# chonkeegamp.net
KiCad netlist of a schematic drawn in EAGLE
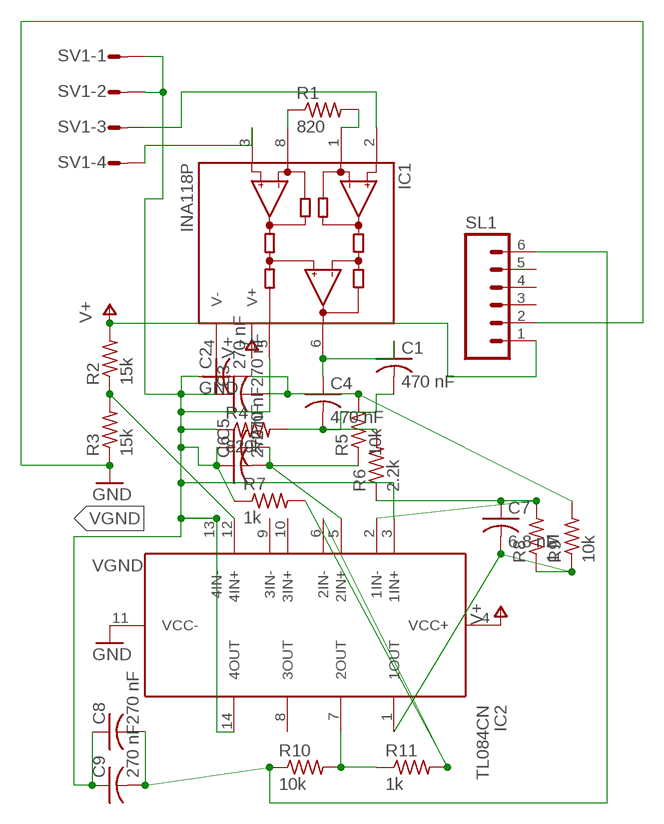
[diagram p0: schematic, sheet 1]

(export (version "E")
  (design (tool "Eeschema 10.0.6"))
  (components
    (comp (ref "C1")
      (value "470 nF")
      (footprint "eagle-import:C050-024X044")
      (fields (field (name "MF") "VISHAY") (field (name "MPN") "BFC237390043"))
      (libsource (lib "eagle-import") (part "C-US050-024X044"))
    )
    (comp (ref "C2")
      (value "270 nF")
      (footprint "eagle-import:C050-024X044")
      (fields (field (name "MF") "VISHAY") (field (name "MPN") "BFC237390132"))
      (libsource (lib "eagle-import") (part "C-US050-024X044"))
    )
    (comp (ref "C3")
      (value "270 nF")
      (footprint "eagle-import:C050-024X044")
      (fields (field (name "MF") "VISHAY") (field (name "MPN") "BFC237390132"))
      (libsource (lib "eagle-import") (part "C-US050-024X044"))
    )
    (comp (ref "C4")
      (value "470 nF")
      (footprint "eagle-import:C050-024X044")
      (fields (field (name "MF") "VISHAY") (field (name "MPN") "BFC237390043"))
      (libsource (lib "eagle-import") (part "C-US050-024X044"))
    )
    (comp (ref "C5")
      (value "270 nF")
      (footprint "eagle-import:C050-024X044")
      (fields (field (name "MF") "VISHAY") (field (name "MPN") "BFC237390132"))
      (libsource (lib "eagle-import") (part "C-US050-024X044"))
    )
    (comp (ref "C6")
      (value "270 nF")
      (footprint "eagle-import:C050-024X044")
      (fields (field (name "MF") "VISHAY") (field (name "MPN") "BFC237390132"))
      (libsource (lib "eagle-import") (part "C-US050-024X044"))
    )
    (comp (ref "C7")
      (value "6.8 nF")
      (footprint "eagle-import:C050-024X044")
      (fields (field (name "MF") "KEMET") (field (name "MPN") "C315C682K1R5TA"))
      (libsource (lib "eagle-import") (part "C-US050-024X044"))
    )
    (comp (ref "C8")
      (value "270 nF")
      (footprint "eagle-import:C050-024X044")
      (fields (field (name "MF") "VISHAY") (field (name "MPN") "BFC237390132"))
      (libsource (lib "eagle-import") (part "C-US050-024X044"))
    )
    (comp (ref "C9")
      (value "270 nF")
      (footprint "eagle-import:C050-024X044")
      (fields (field (name "MF") "VISHAY") (field (name "MPN") "BFC237390132"))
      (libsource (lib "eagle-import") (part "C-US050-024X044"))
    )
    (comp (ref "IC1")
      (value "INA118P")
      (footprint "eagle-import:DIL08")
      (fields (field (name "MF") "TEXAS INSTRUMENTS") (field (name "OC_NEWARK") "34AH0811"))
      (libsource (lib "eagle-import") (part "INA118P"))
    )
    (comp (ref "IC2")
      (value "TL084CN")
      (footprint "eagle-import:DIP794W53P254L1930H508Q14N")
      (fields (field (name "MOUSER_PART_NUMBER") "595-TL084CN") (field (name "MF") "TEXAS INSTRUMENTS"))
      (libsource (lib "eagle-import") (part "TL084CN"))
    )
    (comp (ref "R1")
      (value "820")
      (footprint "eagle-import:0207_7")
      (fields (field (name "MF") "MULTICOMP PRO") (field (name "MPN") "MCF 0.5W 820R"))
      (libsource (lib "eagle-import") (part "R-US_0207/7"))
    )
    (comp (ref "R2")
      (value "15k")
      (footprint "eagle-import:0207_7")
      (fields (field (name "MF") "MULTICOMP PRO") (field (name "MPN") "MCF 1W 15K"))
      (libsource (lib "eagle-import") (part "R-US_0207/7"))
    )
    (comp (ref "R3")
      (value "15k")
      (footprint "eagle-import:0207_7")
      (fields (field (name "MF") "MULTICOMP PRO") (field (name "MPN") "MCF 1W 15K"))
      (libsource (lib "eagle-import") (part "R-US_0207/7"))
    )
    (comp (ref "R4")
      (value "820k")
      (footprint "eagle-import:0207_7")
      (fields (field (name "MF") "MULTICOMP PRO") (field (name "MPN") "MCF 0.25W 820K"))
      (libsource (lib "eagle-import") (part "R-US_0207/7"))
    )
    (comp (ref "R5")
      (value "10k")
      (footprint "eagle-import:0207_7")
      (fields (field (name "MF") "MULTICOMP PRO") (field (name "MPN") "MCCFR0W4J0103A50"))
      (libsource (lib "eagle-import") (part "R-US_0207/7"))
    )
    (comp (ref "R6")
      (value "2.2k")
      (footprint "eagle-import:0207_7")
      (fields (field (name "MF") "MULTICOMP PRO") (field (name "MPN") "MCF 0.5W 2K2"))
      (libsource (lib "eagle-import") (part "R-US_0207/7"))
    )
    (comp (ref "R7")
      (value "1k")
      (footprint "eagle-import:0207_7")
      (fields (field (name "MF") "MULTICOMP PRO") (field (name "MPN") "MCCFR0S2J0102A20"))
      (libsource (lib "eagle-import") (part "R-US_0207/7"))
    )
    (comp (ref "R8")
      (value "1 M")
      (footprint "eagle-import:0207_7")
      (fields (field (name "MF") "MULTICOMP PRO") (field (name "MPN") "MCF 0.5W 1M"))
      (libsource (lib "eagle-import") (part "R-US_0207/7"))
    )
    (comp (ref "R9")
      (value "10k")
      (footprint "eagle-import:0207_7")
      (fields (field (name "MF") "MULTICOMP PRO") (field (name "MPN") "MCCFR0W4J0103A50"))
      (libsource (lib "eagle-import") (part "R-US_0207/7"))
    )
    (comp (ref "R10")
      (value "10k")
      (footprint "eagle-import:0207_7")
      (fields (field (name "MF") "MULTICOMP PRO") (field (name "MPN") "MCCFR0W4J0103A50"))
      (libsource (lib "eagle-import") (part "R-US_0207/7"))
    )
    (comp (ref "R11")
      (value "1k")
      (footprint "eagle-import:0207_7")
      (fields (field (name "MF") "MULTICOMP PRO") (field (name "MPN") "MCCFR0S2J0102A20"))
      (libsource (lib "eagle-import") (part "R-US_0207/7"))
    )
    (comp (ref "SL1")
      (value "M06")
      (footprint "eagle-import:06P")
      (libsource (lib "eagle-import") (part "M06"))
    )
    (comp (ref "SV1")
      (value "L04P")
      (footprint "eagle-import:L04P")
      (libsource (lib "eagle-import") (part "L04P"))
    )
  )
  (nets
    (net (code "1") (name "GND") (class "Default")
      (node (ref "IC1") (pin "4") (pinfunction "V-_4") (pintype "power_in"))
      (node (ref "IC2") (pin "11") (pinfunction "VCC-_11") (pintype "power_in"))
      (node (ref "R3") (pin "1") (pinfunction "1_1") (pintype "passive"))
      (node (ref "SL1") (pin "2") (pinfunction "2_2") (pintype "passive"))
    )
    (net (code "2") (name "Net-(C1-Pad2)") (class "Default")
      (node (ref "C1") (pin "2") (pinfunction "2_2") (pintype "passive"))
      (node (ref "C4") (pin "2") (pinfunction "2_2") (pintype "passive"))
      (node (ref "R4") (pin "2") (pinfunction "2_2") (pintype "passive"))
      (node (ref "R6") (pin "2") (pinfunction "2_2") (pintype "passive"))
    )
    (net (code "3") (name "Net-(C2-Pad2)") (class "Default")
      (node (ref "C2") (pin "2") (pinfunction "2_2") (pintype "passive"))
      (node (ref "C3") (pin "2") (pinfunction "2_2") (pintype "passive"))
      (node (ref "R5") (pin "2") (pinfunction "2_2") (pintype "passive"))
      (node (ref "R9") (pin "2") (pinfunction "2_2") (pintype "passive"))
    )
    (net (code "4") (name "Net-(C8-Pad2)") (class "Default")
      (node (ref "C8") (pin "2") (pinfunction "2_2") (pintype "passive"))
      (node (ref "C9") (pin "2") (pinfunction "2_2") (pintype "passive"))
      (node (ref "R10") (pin "1") (pinfunction "1_1") (pintype "passive"))
      (node (ref "SL1") (pin "6") (pinfunction "6_6") (pintype "passive"))
    )
    (net (code "5") (name "Net-(IC1-+IN)") (class "Default")
      (node (ref "IC1") (pin "3") (pinfunction "+IN_3") (pintype "input"))
      (node (ref "SV1") (pin "4") (pinfunction "S_4") (pintype "passive"))
    )
    (net (code "6") (name "Net-(IC1--IN)") (class "Default")
      (node (ref "IC1") (pin "2") (pinfunction "-IN_2") (pintype "input"))
      (node (ref "SV1") (pin "3") (pinfunction "S_3") (pintype "passive"))
    )
    (net (code "7") (name "Net-(IC1-OUT)") (class "Default")
      (node (ref "C1") (pin "1") (pinfunction "1_1") (pintype "passive"))
      (node (ref "C4") (pin "1") (pinfunction "1_1") (pintype "passive"))
      (node (ref "IC1") (pin "6") (pinfunction "OUT_6") (pintype "output"))
    )
    (net (code "8") (name "Net-(IC1-RG-Pad1)") (class "Default")
      (node (ref "IC1") (pin "1") (pinfunction "RG_1") (pintype "passive"))
      (node (ref "R1") (pin "2") (pinfunction "2_2") (pintype "passive"))
    )
    (net (code "9") (name "Net-(IC1-RG-Pad8)") (class "Default")
      (node (ref "IC1") (pin "8") (pinfunction "RG_8") (pintype "passive"))
      (node (ref "R1") (pin "1") (pinfunction "1_1") (pintype "passive"))
    )
    (net (code "10") (name "Net-(IC2-1IN-)") (class "Default")
      (node (ref "C7") (pin "1") (pinfunction "1_1") (pintype "passive"))
      (node (ref "IC2") (pin "2") (pinfunction "1IN-_2") (pintype "input"))
      (node (ref "R6") (pin "1") (pinfunction "1_1") (pintype "passive"))
      (node (ref "R8") (pin "2") (pinfunction "2_2") (pintype "passive"))
    )
    (net (code "11") (name "Net-(IC2-1OUT)") (class "Default")
      (node (ref "C7") (pin "2") (pinfunction "2_2") (pintype "passive"))
      (node (ref "IC2") (pin "1") (pinfunction "1OUT_1") (pintype "output"))
      (node (ref "R8") (pin "1") (pinfunction "1_1") (pintype "passive"))
      (node (ref "R9") (pin "1") (pinfunction "1_1") (pintype "passive"))
    )
    (net (code "12") (name "Net-(IC2-2IN+)") (class "Default")
      (node (ref "C5") (pin "2") (pinfunction "2_2") (pintype "passive"))
      (node (ref "C6") (pin "2") (pinfunction "2_2") (pintype "passive"))
      (node (ref "IC2") (pin "5") (pinfunction "2IN+_5") (pintype "input"))
      (node (ref "R5") (pin "1") (pinfunction "1_1") (pintype "passive"))
    )
    (net (code "13") (name "Net-(IC2-2IN-)") (class "Default")
      (node (ref "IC2") (pin "6") (pinfunction "2IN-_6") (pintype "input"))
      (node (ref "R11") (pin "2") (pinfunction "2_2") (pintype "passive"))
      (node (ref "R7") (pin "2") (pinfunction "2_2") (pintype "passive"))
    )
    (net (code "14") (name "Net-(IC2-2OUT)") (class "Default")
      (node (ref "IC2") (pin "7") (pinfunction "2OUT_7") (pintype "output"))
      (node (ref "R10") (pin "2") (pinfunction "2_2") (pintype "passive"))
      (node (ref "R11") (pin "1") (pinfunction "1_1") (pintype "passive"))
    )
    (net (code "15") (name "Net-(IC2-4IN+)") (class "Default")
      (node (ref "IC2") (pin "12") (pinfunction "4IN+_12") (pintype "input"))
      (node (ref "R2") (pin "1") (pinfunction "1_1") (pintype "passive"))
      (node (ref "R3") (pin "2") (pinfunction "2_2") (pintype "passive"))
    )
    (net (code "16") (name "V+") (class "Default")
      (node (ref "IC1") (pin "7") (pinfunction "V+_7") (pintype "power_in"))
      (node (ref "IC2") (pin "4") (pinfunction "VCC+_4") (pintype "power_in"))
      (node (ref "R2") (pin "2") (pinfunction "2_2") (pintype "passive"))
      (node (ref "SL1") (pin "1") (pinfunction "1_1") (pintype "passive"))
    )
    (net (code "17") (name "VGND") (class "Default")
      (node (ref "C2") (pin "1") (pinfunction "1_1") (pintype "passive"))
      (node (ref "C3") (pin "1") (pinfunction "1_1") (pintype "passive"))
      (node (ref "C5") (pin "1") (pinfunction "1_1") (pintype "passive"))
      (node (ref "C6") (pin "1") (pinfunction "1_1") (pintype "passive"))
      (node (ref "C8") (pin "1") (pinfunction "1_1") (pintype "passive"))
      (node (ref "C9") (pin "1") (pinfunction "1_1") (pintype "passive"))
      (node (ref "IC1") (pin "5") (pinfunction "REF_5") (pintype "passive"))
      (node (ref "IC2") (pin "13") (pinfunction "4IN-_13") (pintype "input"))
      (node (ref "IC2") (pin "14") (pinfunction "4OUT_14") (pintype "output"))
      (node (ref "IC2") (pin "3") (pinfunction "1IN+_3") (pintype "input"))
      (node (ref "R4") (pin "1") (pinfunction "1_1") (pintype "passive"))
      (node (ref "R7") (pin "1") (pinfunction "1_1") (pintype "passive"))
      (node (ref "SV1") (pin "1") (pinfunction "S_1") (pintype "passive"))
      (node (ref "SV1") (pin "2") (pinfunction "S_2") (pintype "passive"))
    )
    (net (code "18") (name "unconnected-(IC2-3IN+-Pad10)") (class "Default")
      (node (ref "IC2") (pin "10") (pinfunction "3IN+_10") (pintype "input"))
    )
    (net (code "19") (name "unconnected-(IC2-3IN--Pad9)") (class "Default")
      (node (ref "IC2") (pin "9") (pinfunction "3IN-_9") (pintype "input"))
    )
    (net (code "20") (name "unconnected-(IC2-3OUT-Pad8)") (class "Default")
      (node (ref "IC2") (pin "8") (pinfunction "3OUT_8") (pintype "output"))
    )
    (net (code "21") (name "unconnected-(SL1-Pad3)") (class "Default")
      (node (ref "SL1") (pin "3") (pinfunction "3_3") (pintype "passive"))
    )
    (net (code "22") (name "unconnected-(SL1-Pad4)") (class "Default")
      (node (ref "SL1") (pin "4") (pinfunction "4_4") (pintype "passive"))
    )
    (net (code "23") (name "unconnected-(SL1-Pad5)") (class "Default")
      (node (ref "SL1") (pin "5") (pinfunction "5_5") (pintype "passive"))
    )
  )
)
